# Micro.net
KiCad netlist of a schematic drawn in EAGLE
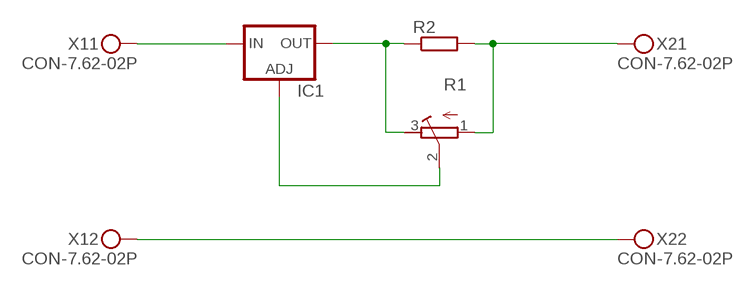
[diagram p0: schematic, sheet 1]

(export (version "E")
  (design (tool "Eeschema 10.0.6"))
  (components
    (comp (ref "IC1")
      (value "LM350T")
      (footprint "eagle-import:317TS")
      (libsource (lib "eagle-import") (part "LM350T"))
    )
    (comp (ref "R1")
      (value "R_POTE")
      (footprint "eagle-import:EVUE")
      (libsource (lib "eagle-import") (part "R_POTE"))
    )
    (comp (ref "R2")
      (value "R_SQP-5")
      (footprint "eagle-import:SQP-5")
      (libsource (lib "eagle-import") (part "R_SQP-5"))
    )
    (comp (ref "X1")
      (value "CON-7.62-02P")
      (footprint "eagle-import:KF25C-7.62-02P-13")
      (libsource (lib "eagle-import") (part "CON-7.62-02P"))
    )
    (comp (ref "X2")
      (value "CON-7.62-02P")
      (footprint "eagle-import:KF25C-7.62-02P-13")
      (libsource (lib "eagle-import") (part "CON-7.62-02P"))
    )
  )
  (nets
    (net (code "1") (name "Net-(IC1-ADJ)") (class "Default")
      (node (ref "IC1") (pin "1") (pinfunction "ADJ_1") (pintype "input"))
      (node (ref "R1") (pin "2") (pinfunction "S_2") (pintype "passive"))
    )
    (net (code "2") (name "Net-(IC1-IN)") (class "Default")
      (node (ref "IC1") (pin "3") (pinfunction "IN_3") (pintype "input"))
      (node (ref "X1") (pin "P$1") (pinfunction "KL_P$1") (pintype "passive"))
    )
    (net (code "3") (name "Net-(IC1-OUT)") (class "Default")
      (node (ref "IC1") (pin "2") (pinfunction "OUT_2") (pintype "passive"))
      (node (ref "R1") (pin "3") (pinfunction "E_3") (pintype "passive"))
      (node (ref "R2") (pin "1") (pinfunction "1_1") (pintype "passive"))
    )
    (net (code "4") (name "Net-(R1-A)") (class "Default")
      (node (ref "R1") (pin "1") (pinfunction "A_1") (pintype "passive"))
      (node (ref "R2") (pin "2") (pinfunction "2_2") (pintype "passive"))
      (node (ref "X2") (pin "P$1") (pinfunction "KL_P$1") (pintype "passive"))
    )
    (net (code "5") (name "Net-(X1B-KL)") (class "Default")
      (node (ref "X1") (pin "P$2") (pinfunction "KL_P$2") (pintype "passive"))
      (node (ref "X2") (pin "P$2") (pinfunction "KL_P$2") (pintype "passive"))
    )
  )
)
